# mbedshield042.net
KiCad netlist of a schematic drawn in EAGLE
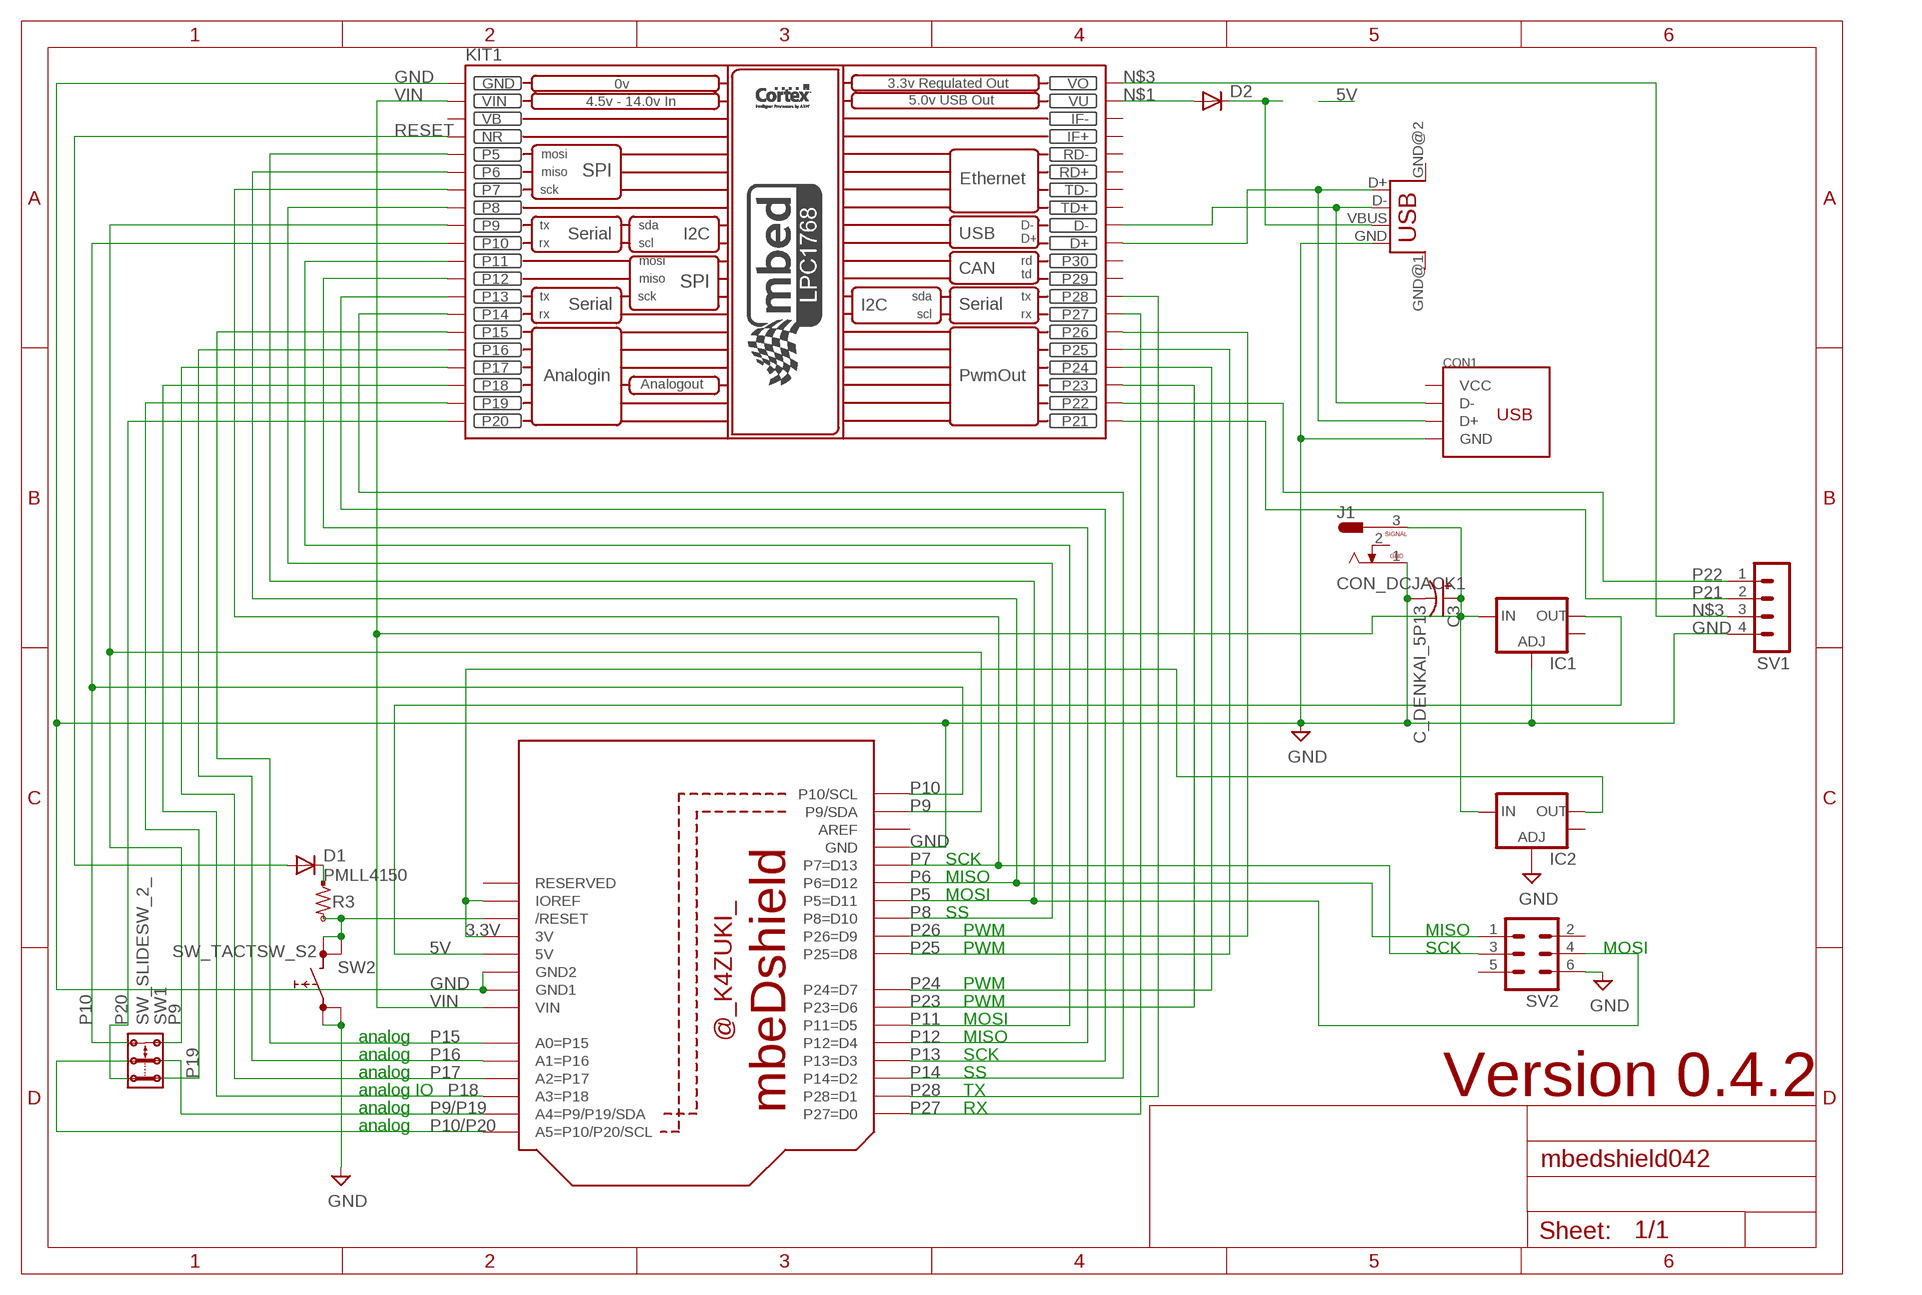
[diagram p0: schematic, sheet 1]

(export (version "E")
  (design (tool "Eeschema 10.0.6"))
  (components
    (comp (ref "C3")
      (value "C_DENKAI_5P13")
      (footprint "eagle-import:153CLV-1014")
      (libsource (lib "eagle-import") (part "CPOL-US153CLV-1014"))
    )
    (comp (ref "CON1")
      (value "CON_USB")
      (footprint "eagle-import:CON_USB_MINIB_AKI")
      (libsource (lib "eagle-import") (part "CON_USB"))
    )
    (comp (ref "D1")
      (value "PMLL4150")
      (footprint "eagle-import:SOD80C")
      (libsource (lib "eagle-import") (part "PMLL4150"))
    )
    (comp (ref "D2")
      (value "PMLL4150")
      (footprint "eagle-import:SOD80C")
      (libsource (lib "eagle-import") (part "PMLL4150"))
    )
    (comp (ref "IC1")
      (value "V_REG_LM1117SOT223")
      (footprint "eagle-import:SOT223")
      (libsource (lib "eagle-import") (part "V_REG_LM1117SOT223"))
    )
    (comp (ref "IC2")
      (value "V_REG_LM1117SOT223")
      (footprint "eagle-import:SOT223")
      (libsource (lib "eagle-import") (part "V_REG_LM1117SOT223"))
    )
    (comp (ref "J1")
      (value "CON_DCJACK1")
      (footprint "eagle-import:CON_DCJACK")
      (libsource (lib "eagle-import") (part "CON_DCJACK1"))
    )
    (comp (ref "KIT1")
      (value "MBED_NXP_LPC1768")
      (footprint "eagle-import:MBED-KIT")
      (libsource (lib "eagle-import") (part "MBED_NXP_LPC1768"))
    )
    (comp (ref "R3")
      (value "R_US_PAD_VIA_2125")
      (footprint "eagle-import:R_2125_PADVIA")
      (libsource (lib "eagle-import") (part "R_US_PAD_VIA_2125"))
    )
    (comp (ref "SV1")
      (value "MA04-1")
      (footprint "eagle-import:MA04-1")
      (libsource (lib "eagle-import") (part "MA04-1"))
    )
    (comp (ref "SV2")
      (value "MA03-2")
      (footprint "eagle-import:MA03-2")
      (libsource (lib "eagle-import") (part "MA03-2"))
    )
    (comp (ref "SW1")
      (value "SW_SLIDESW_2_")
      (footprint "eagle-import:SW_SLIDE_2X2_1")
      (libsource (lib "eagle-import") (part "SW_SLIDESW_2_"))
    )
    (comp (ref "SW2")
      (value "SW_TACTSW_S2")
      (footprint "eagle-import:SW_TACTSW_B3F-10XX")
      (libsource (lib "eagle-import") (part "SW_TACTSW_S2"))
    )
    (comp (ref "U$1")
      (value "BOARD_MBEDSHIELD")
      (footprint "eagle-import:BOARD_MBEDSHIOELD")
      (libsource (lib "eagle-import") (part "BOARD_MBEDSHIELD"))
    )
    (comp (ref "USB")
      (value "USB")
      (footprint "eagle-import:USB-FEMALE-A-PTH")
      (libsource (lib "eagle-import") (part "USB"))
    )
  )
  (nets
    (net (code "1") (name "/3.3V") (class "Default")
      (node (ref "IC2") (pin "2") (pinfunction "OUT_2") (pintype "output"))
      (node (ref "U$1") (pin "3V") (pinfunction "3V_3V") (pintype "power_in"))
      (node (ref "U$1") (pin "IOREF") (pinfunction "IOREF_IOREF") (pintype "output"))
    )
    (net (code "2") (name "/5V") (class "Default")
      (node (ref "IC1") (pin "2") (pinfunction "OUT_2") (pintype "output"))
      (node (ref "U$1") (pin "5V") (pinfunction "5V_5V") (pintype "power_in"))
    )
    (net (code "3") (name "/N$1") (class "Default")
      (node (ref "D2") (pin "A") (pinfunction "A_A") (pintype "passive"))
      (node (ref "KIT1") (pin "VU") (pinfunction "VU_VU") (pintype "power_in"))
    )
    (net (code "4") (name "/N$3") (class "Default")
      (node (ref "KIT1") (pin "VOUT") (pinfunction "VO_VOUT") (pintype "power_in"))
      (node (ref "SV1") (pin "3") (pinfunction "3_3") (pintype "passive"))
    )
    (net (code "5") (name "/P5") (class "Default")
      (node (ref "KIT1") (pin "P$5") (pinfunction "P5_P$5") (pintype "bidirectional"))
      (node (ref "SV2") (pin "4") (pinfunction "4_4") (pintype "passive"))
      (node (ref "U$1") (pin "D11") (pinfunction "P5=D11_D11") (pintype "bidirectional"))
    )
    (net (code "6") (name "/P6") (class "Default")
      (node (ref "KIT1") (pin "P$6") (pinfunction "P6_P$6") (pintype "bidirectional"))
      (node (ref "SV2") (pin "1") (pinfunction "1_1") (pintype "passive"))
      (node (ref "U$1") (pin "D12") (pinfunction "P6=D12_D12") (pintype "bidirectional"))
    )
    (net (code "7") (name "/P7") (class "Default")
      (node (ref "KIT1") (pin "P$7") (pinfunction "P7_P$7") (pintype "bidirectional"))
      (node (ref "SV2") (pin "3") (pinfunction "3_3") (pintype "passive"))
      (node (ref "U$1") (pin "D13") (pinfunction "P7=D13_D13") (pintype "bidirectional"))
    )
    (net (code "8") (name "/P8") (class "Default")
      (node (ref "KIT1") (pin "P$8") (pinfunction "P8_P$8") (pintype "bidirectional"))
      (node (ref "U$1") (pin "D10") (pinfunction "P8=D10_D10") (pintype "bidirectional"))
    )
    (net (code "9") (name "/P9") (class "Default")
      (node (ref "KIT1") (pin "P$9") (pinfunction "P9_P$9") (pintype "bidirectional"))
      (node (ref "SW1") (pin "2.1") (pinfunction "2.1_2.1") (pintype "passive"))
      (node (ref "U$1") (pin "SDA") (pinfunction "P9/SDA_SDA") (pintype "bidirectional"))
    )
    (net (code "10") (name "/P9{slash}P19") (class "Default")
      (node (ref "SW1") (pin "COM.1") (pinfunction "COM.1_COM.1") (pintype "passive"))
      (node (ref "U$1") (pin "A4") (pinfunction "A4=P9/P19/SDA_A4") (pintype "bidirectional"))
    )
    (net (code "11") (name "/P10") (class "Default")
      (node (ref "KIT1") (pin "P$10") (pinfunction "P10_P$10") (pintype "bidirectional"))
      (node (ref "SW1") (pin "2.2") (pinfunction "2.2_2.2") (pintype "passive"))
      (node (ref "U$1") (pin "SCL") (pinfunction "P10/SCL_SCL") (pintype "bidirectional"))
    )
    (net (code "12") (name "/P10{slash}P20") (class "Default")
      (node (ref "SW1") (pin "COM.2") (pinfunction "COM.2_COM.2") (pintype "passive"))
      (node (ref "U$1") (pin "A5") (pinfunction "A5=P10/P20/SCL_A5") (pintype "bidirectional"))
    )
    (net (code "13") (name "/P11") (class "Default")
      (node (ref "KIT1") (pin "P$11") (pinfunction "P11_P$11") (pintype "bidirectional"))
      (node (ref "U$1") (pin "D5") (pinfunction "P11=D5_D5") (pintype "bidirectional"))
    )
    (net (code "14") (name "/P12") (class "Default")
      (node (ref "KIT1") (pin "P$12") (pinfunction "P12_P$12") (pintype "bidirectional"))
      (node (ref "U$1") (pin "D4") (pinfunction "P12=D4_D4") (pintype "bidirectional"))
    )
    (net (code "15") (name "/P13") (class "Default")
      (node (ref "KIT1") (pin "P$13") (pinfunction "P13_P$13") (pintype "bidirectional"))
      (node (ref "U$1") (pin "D3") (pinfunction "P13=D3_D3") (pintype "bidirectional"))
    )
    (net (code "16") (name "/P14") (class "Default")
      (node (ref "KIT1") (pin "P$14") (pinfunction "P14_P$14") (pintype "bidirectional"))
      (node (ref "U$1") (pin "D2") (pinfunction "P14=D2_D2") (pintype "bidirectional"))
    )
    (net (code "17") (name "/P15") (class "Default")
      (node (ref "KIT1") (pin "P$15") (pinfunction "P15_P$15") (pintype "bidirectional"))
      (node (ref "U$1") (pin "A0") (pinfunction "A0=P15_A0") (pintype "bidirectional"))
    )
    (net (code "18") (name "/P16") (class "Default")
      (node (ref "KIT1") (pin "P$16") (pinfunction "P16_P$16") (pintype "bidirectional"))
      (node (ref "U$1") (pin "A1") (pinfunction "A1=P16_A1") (pintype "bidirectional"))
    )
    (net (code "19") (name "/P17") (class "Default")
      (node (ref "KIT1") (pin "P$17") (pinfunction "P17_P$17") (pintype "bidirectional"))
      (node (ref "U$1") (pin "A2") (pinfunction "A2=P17_A2") (pintype "bidirectional"))
    )
    (net (code "20") (name "/P18") (class "Default")
      (node (ref "KIT1") (pin "P$18") (pinfunction "P18_P$18") (pintype "bidirectional"))
      (node (ref "U$1") (pin "A3") (pinfunction "A3=P18_A3") (pintype "bidirectional"))
    )
    (net (code "21") (name "/P19") (class "Default")
      (node (ref "KIT1") (pin "P$19") (pinfunction "P19_P$19") (pintype "bidirectional"))
      (node (ref "SW1") (pin "1.1") (pinfunction "1.1_1.1") (pintype "passive"))
    )
    (net (code "22") (name "/P20") (class "Default")
      (node (ref "KIT1") (pin "P$20") (pinfunction "P20_P$20") (pintype "bidirectional"))
      (node (ref "SW1") (pin "1.2") (pinfunction "1.2_1.2") (pintype "passive"))
    )
    (net (code "23") (name "/P21") (class "Default")
      (node (ref "KIT1") (pin "P$21") (pinfunction "P21_P$21") (pintype "bidirectional"))
      (node (ref "SV1") (pin "2") (pinfunction "2_2") (pintype "passive"))
    )
    (net (code "24") (name "/P22") (class "Default")
      (node (ref "KIT1") (pin "P$22") (pinfunction "P22_P$22") (pintype "bidirectional"))
      (node (ref "SV1") (pin "1") (pinfunction "1_1") (pintype "passive"))
    )
    (net (code "25") (name "/P23") (class "Default")
      (node (ref "KIT1") (pin "P$23") (pinfunction "P23_P$23") (pintype "bidirectional"))
      (node (ref "U$1") (pin "D6") (pinfunction "P23=D6_D6") (pintype "bidirectional"))
    )
    (net (code "26") (name "/P24") (class "Default")
      (node (ref "KIT1") (pin "P$24") (pinfunction "P24_P$24") (pintype "bidirectional"))
      (node (ref "U$1") (pin "D7") (pinfunction "P24=D7_D7") (pintype "bidirectional"))
    )
    (net (code "27") (name "/P25") (class "Default")
      (node (ref "KIT1") (pin "P$25") (pinfunction "P25_P$25") (pintype "bidirectional"))
      (node (ref "U$1") (pin "D8") (pinfunction "P25=D8_D8") (pintype "bidirectional"))
    )
    (net (code "28") (name "/P26") (class "Default")
      (node (ref "KIT1") (pin "P$26") (pinfunction "P26_P$26") (pintype "bidirectional"))
      (node (ref "U$1") (pin "D9") (pinfunction "P26=D9_D9") (pintype "bidirectional"))
    )
    (net (code "29") (name "/P27") (class "Default")
      (node (ref "KIT1") (pin "P$27") (pinfunction "P27_P$27") (pintype "bidirectional"))
      (node (ref "U$1") (pin "D0") (pinfunction "P27=D0_D0") (pintype "bidirectional"))
    )
    (net (code "30") (name "/P28") (class "Default")
      (node (ref "KIT1") (pin "P$28") (pinfunction "P28_P$28") (pintype "bidirectional"))
      (node (ref "U$1") (pin "D1") (pinfunction "P28=D1_D1") (pintype "bidirectional"))
    )
    (net (code "31") (name "/RESET") (class "Default")
      (node (ref "D1") (pin "A") (pinfunction "A_A") (pintype "passive"))
      (node (ref "KIT1") (pin "NR") (pinfunction "NR_NR") (pintype "power_in"))
    )
    (net (code "32") (name "/VB") (class "Default")
      (node (ref "KIT1") (pin "VB") (pinfunction "VB_VB") (pintype "power_in"))
    )
    (net (code "33") (name "/VIN") (class "Default")
      (node (ref "C3") (pin "+") (pinfunction "+_+") (pintype "passive"))
      (node (ref "IC1") (pin "3") (pinfunction "IN_3") (pintype "input"))
      (node (ref "IC2") (pin "3") (pinfunction "IN_3") (pintype "input"))
      (node (ref "J1") (pin "3") (pinfunction "1_3") (pintype "passive"))
      (node (ref "KIT1") (pin "VIN") (pinfunction "VIN_VIN") (pintype "power_in"))
      (node (ref "U$1") (pin "VIN") (pinfunction "VIN_VIN") (pintype "power_in"))
    )
    (net (code "34") (name "GND") (class "Default")
      (node (ref "C3") (pin "-") (pinfunction "-_-") (pintype "passive"))
      (node (ref "CON1") (pin "GND") (pinfunction "GND_GND") (pintype "bidirectional"))
      (node (ref "IC1") (pin "1") (pinfunction "ADJ_1") (pintype "input"))
      (node (ref "IC2") (pin "1") (pinfunction "ADJ_1") (pintype "input"))
      (node (ref "J1") (pin "1") (pinfunction "3_1") (pintype "passive"))
      (node (ref "KIT1") (pin "GND") (pinfunction "GND_GND") (pintype "power_in"))
      (node (ref "SV1") (pin "4") (pinfunction "4_4") (pintype "passive"))
      (node (ref "SV2") (pin "6") (pinfunction "6_6") (pintype "passive"))
      (node (ref "SW2") (pin "1") (pinfunction "0_1") (pintype "passive"))
      (node (ref "SW2") (pin "2") (pinfunction "0_2") (pintype "passive"))
      (node (ref "U$1") (pin "GND") (pinfunction "GND_GND") (pintype "power_in"))
      (node (ref "U$1") (pin "GND1") (pinfunction "GND1_GND1") (pintype "power_in"))
      (node (ref "U$1") (pin "GND2") (pinfunction "GND2_GND2") (pintype "power_in"))
      (node (ref "USB") (pin "GND") (pinfunction "GND_GND") (pintype "bidirectional"))
    )
    (net (code "35") (name "Net-(CON1-PadD+)") (class "Default")
      (node (ref "CON1") (pin "D+") (pinfunction "D+_D+") (pintype "bidirectional"))
      (node (ref "KIT1") (pin "D+") (pinfunction "D+_D+") (pintype "bidirectional"))
      (node (ref "USB") (pin "D+") (pinfunction "D+_D+") (pintype "bidirectional"))
    )
    (net (code "36") (name "Net-(CON1-PadD-)") (class "Default")
      (node (ref "CON1") (pin "D-") (pinfunction "D-_D-") (pintype "bidirectional"))
      (node (ref "KIT1") (pin "D-") (pinfunction "D-_D-") (pintype "bidirectional"))
      (node (ref "USB") (pin "D-") (pinfunction "D-_D-") (pintype "bidirectional"))
    )
    (net (code "37") (name "Net-(D1-PadC)") (class "Default")
      (node (ref "D1") (pin "C") (pinfunction "C_C") (pintype "passive"))
      (node (ref "R3") (pin "PAD") (pinfunction "PAD_PAD") (pintype "passive"))
    )
    (net (code "38") (name "Net-(D2-PadC)") (class "Default")
      (node (ref "D2") (pin "C") (pinfunction "C_C") (pintype "passive"))
      (node (ref "USB") (pin "VBUS") (pinfunction "VBUS_VBUS") (pintype "bidirectional"))
    )
    (net (code "39") (name "Net-(U$1-{slash}RESET)") (class "Default")
      (node (ref "R3") (pin "VIA") (pinfunction "VIA_VIA") (pintype "passive"))
      (node (ref "SW2") (pin "3") (pinfunction "1_3") (pintype "passive"))
      (node (ref "SW2") (pin "4") (pinfunction "1_4") (pintype "passive"))
      (node (ref "U$1") (pin "RESET") (pinfunction "/RESET_RESET") (pintype "bidirectional"))
    )
    (net (code "40") (name "unconnected-(CON1-VCC-PadVBUS)") (class "Default")
      (node (ref "CON1") (pin "VBUS") (pinfunction "VCC_VBUS") (pintype "bidirectional"))
    )
    (net (code "41") (name "unconnected-(IC1-OUT-Pad4)") (class "Default")
      (node (ref "IC1") (pin "4") (pinfunction "OUT_4") (pintype "output"))
    )
    (net (code "42") (name "unconnected-(IC2-OUT-Pad4)") (class "Default")
      (node (ref "IC2") (pin "4") (pinfunction "OUT_4") (pintype "output"))
    )
    (net (code "43") (name "unconnected-(J1-Pad2)") (class "Default")
      (node (ref "J1") (pin "2") (pinfunction "2_2") (pintype "passive"))
    )
    (net (code "44") (name "unconnected-(KIT1-P29-PadP$29)") (class "Default")
      (node (ref "KIT1") (pin "P$29") (pinfunction "P29_P$29") (pintype "bidirectional"))
    )
    (net (code "45") (name "unconnected-(KIT1-P30-PadP$30)") (class "Default")
      (node (ref "KIT1") (pin "P$30") (pinfunction "P30_P$30") (pintype "bidirectional"))
    )
    (net (code "46") (name "unconnected-(KIT1-PadIF+)") (class "Default")
      (node (ref "KIT1") (pin "IF+") (pinfunction "IF+_IF+") (pintype "bidirectional"))
    )
    (net (code "47") (name "unconnected-(KIT1-PadIF-)") (class "Default")
      (node (ref "KIT1") (pin "IF-") (pinfunction "IF-_IF-") (pintype "bidirectional"))
    )
    (net (code "48") (name "unconnected-(KIT1-PadRD+)") (class "Default")
      (node (ref "KIT1") (pin "RD+") (pinfunction "RD+_RD+") (pintype "bidirectional"))
    )
    (net (code "49") (name "unconnected-(KIT1-PadRD-)") (class "Default")
      (node (ref "KIT1") (pin "RD-") (pinfunction "RD-_RD-") (pintype "bidirectional"))
    )
    (net (code "50") (name "unconnected-(KIT1-PadTD+)") (class "Default")
      (node (ref "KIT1") (pin "TD+") (pinfunction "TD+_TD+") (pintype "bidirectional"))
    )
    (net (code "51") (name "unconnected-(KIT1-PadTD-)") (class "Default")
      (node (ref "KIT1") (pin "TD-") (pinfunction "TD-_TD-") (pintype "bidirectional"))
    )
    (net (code "52") (name "unconnected-(SV2-Pad2)") (class "Default")
      (node (ref "SV2") (pin "2") (pinfunction "2_2") (pintype "passive"))
    )
    (net (code "53") (name "unconnected-(SV2-Pad5)") (class "Default")
      (node (ref "SV2") (pin "5") (pinfunction "5_5") (pintype "passive"))
    )
    (net (code "54") (name "unconnected-(U$1-PadAREF)") (class "Default")
      (node (ref "U$1") (pin "AREF") (pinfunction "AREF_AREF") (pintype "bidirectional"))
    )
    (net (code "55") (name "unconnected-(U$1-PadRESERVED)") (class "Default")
      (node (ref "U$1") (pin "RESERVED") (pinfunction "RESERVED_RESERVED") (pintype "no_connect"))
    )
    (net (code "56") (name "unconnected-(USB-GND-PadGND@1)") (class "Default")
      (node (ref "USB") (pin "GND@1") (pinfunction "GND_GND@1") (pintype "bidirectional"))
    )
    (net (code "57") (name "unconnected-(USB-GND-PadGND@2)") (class "Default")
      (node (ref "USB") (pin "GND@2") (pinfunction "GND_GND@2") (pintype "bidirectional"))
    )
  )
)
